# BOTTOM_BRD_v_1_0_3b.net
KiCad netlist of a schematic drawn in EAGLE
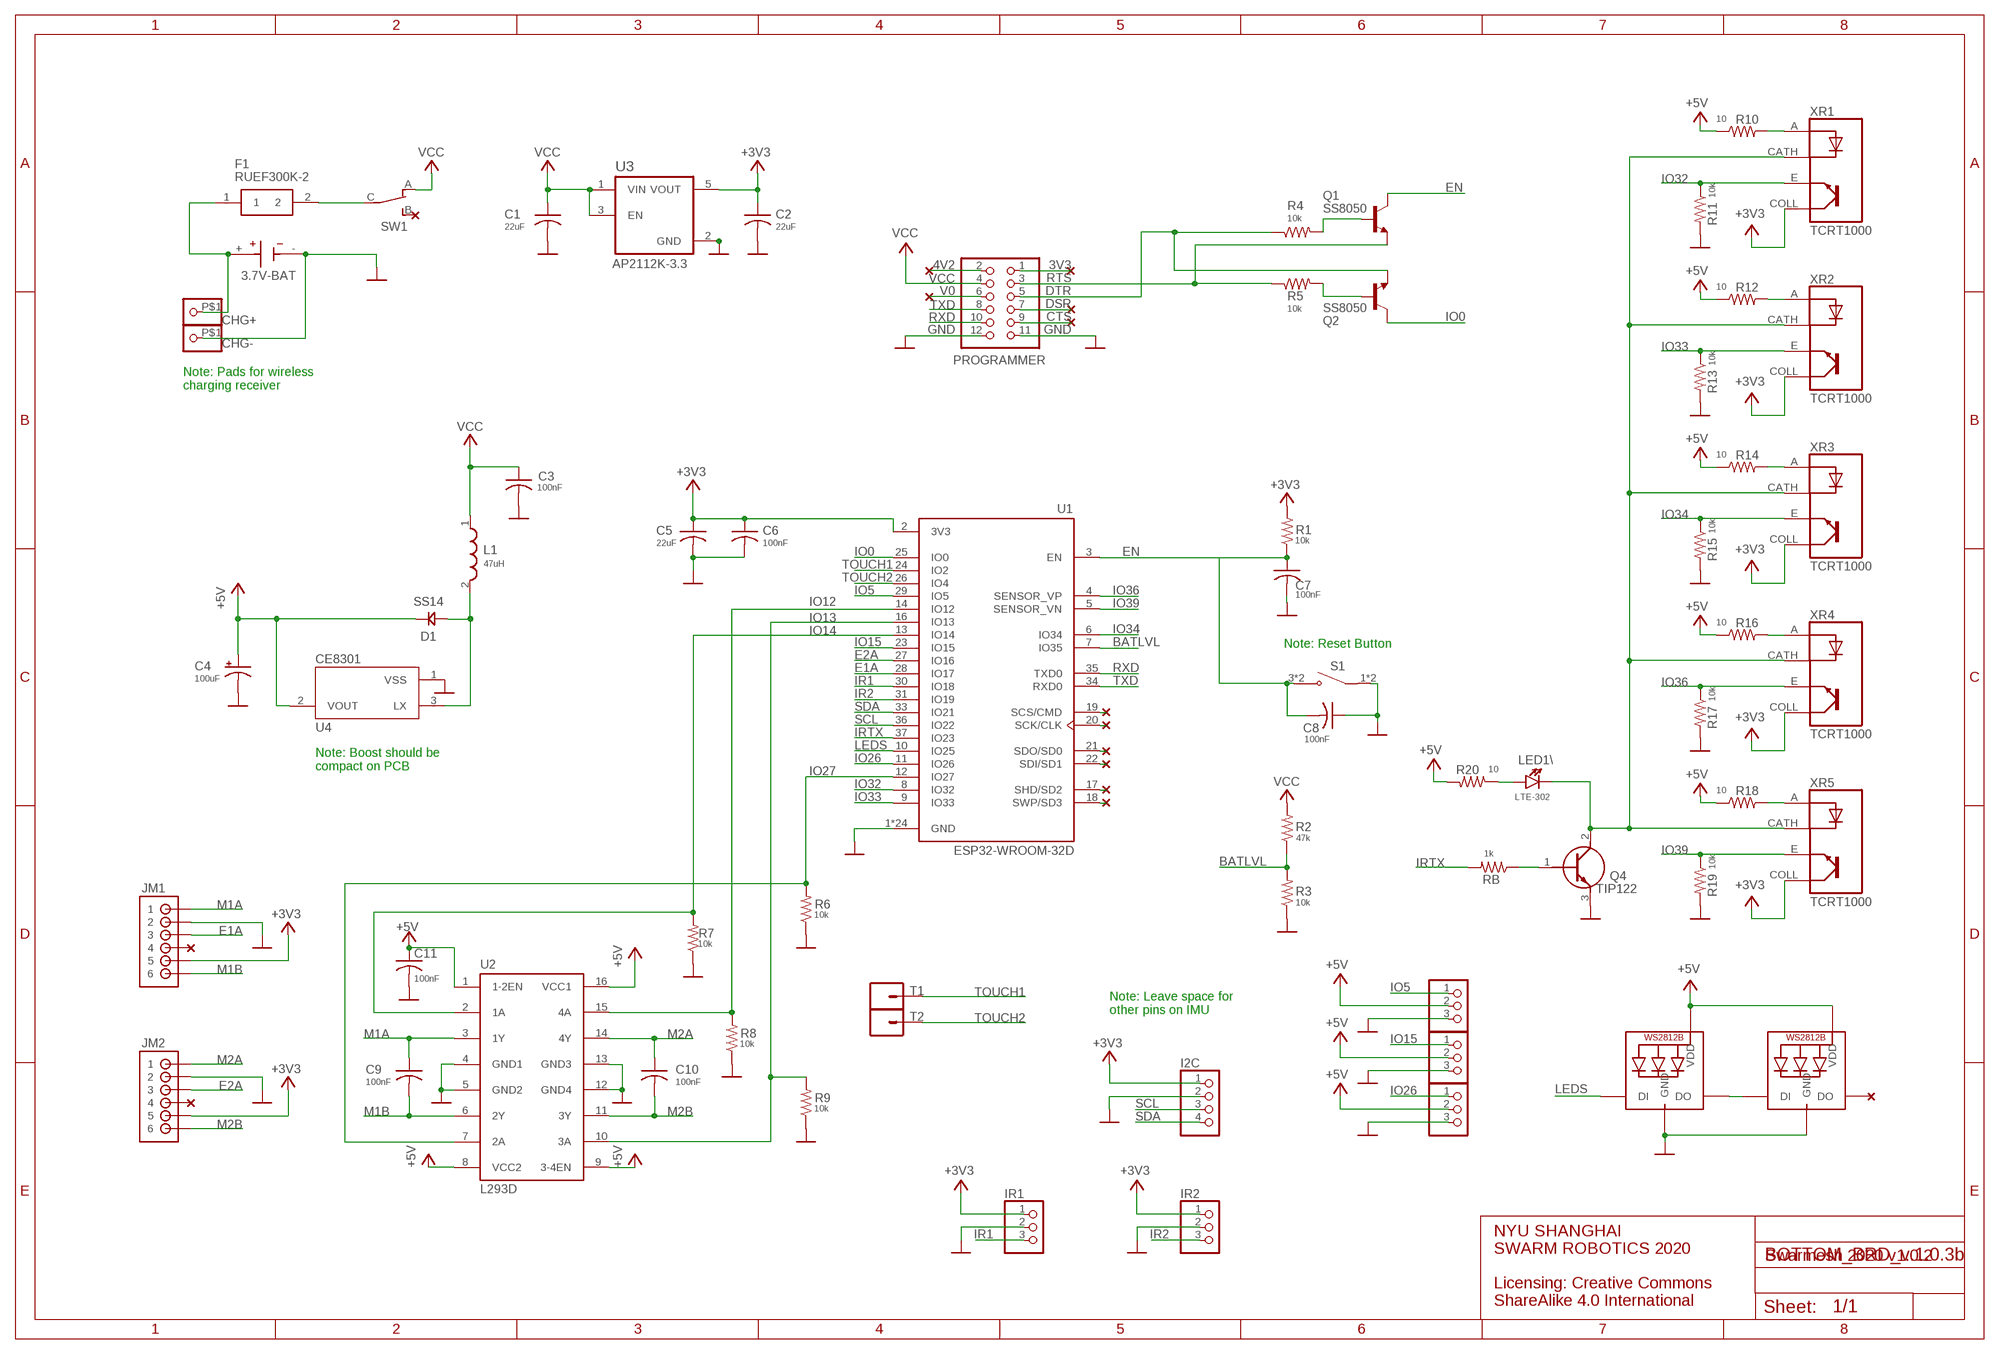
[diagram p0: schematic, sheet 1]

(export (version "E")
  (design (tool "Eeschema 10.0.6"))
  (components
    (comp (ref "BT")
      (value "3.7V-BAT")
      (footprint "eagle-import:BAT_6S-AA")
      (fields (field (name "MF") "MPD") (field (name "MP") "6S-AA"))
      (libsource (lib "eagle-import") (part "6S-AA"))
    )
    (comp (ref "C1")
      (value "22uF")
      (footprint "eagle-import:C0805")
      (libsource (lib "eagle-import") (part "C-USC0805"))
    )
    (comp (ref "C2")
      (value "22uF")
      (footprint "eagle-import:C0805")
      (libsource (lib "eagle-import") (part "C-USC0805"))
    )
    (comp (ref "C3")
      (value "100nF")
      (footprint "eagle-import:C0805")
      (libsource (lib "eagle-import") (part "C-USC0805"))
    )
    (comp (ref "C4")
      (value "100uF")
      (footprint "eagle-import:153CLV-0605")
      (libsource (lib "eagle-import") (part "CPOL-US153CLV-0605"))
    )
    (comp (ref "C5")
      (value "22uF")
      (footprint "eagle-import:C0805")
      (libsource (lib "eagle-import") (part "C-USC0805"))
    )
    (comp (ref "C6")
      (value "100nF")
      (footprint "eagle-import:C0805")
      (libsource (lib "eagle-import") (part "C-USC0805"))
    )
    (comp (ref "C7")
      (value "100nF")
      (footprint "eagle-import:C0805")
      (libsource (lib "eagle-import") (part "C-USC0805"))
    )
    (comp (ref "C8")
      (value "100nF")
      (footprint "eagle-import:C0805")
      (libsource (lib "eagle-import") (part "C-USC0805"))
    )
    (comp (ref "C9")
      (value "100nF")
      (footprint "eagle-import:C0805")
      (libsource (lib "eagle-import") (part "C-USC0805"))
    )
    (comp (ref "C10")
      (value "100nF")
      (footprint "eagle-import:C0805")
      (libsource (lib "eagle-import") (part "C-USC0805"))
    )
    (comp (ref "C11")
      (value "100nF")
      (footprint "eagle-import:C0805")
      (libsource (lib "eagle-import") (part "C-USC0805"))
    )
    (comp (ref "CHARGING")
      (value "WS2812B5050")
      (footprint "eagle-import:WS2812B")
      (libsource (lib "eagle-import") (part "WS2812B5050"))
    )
    (comp (ref "CHG+")
      (value "PINHD-1X1-BIGPOGO")
      (footprint "eagle-import:1X1-BIGPOGO")
      (libsource (lib "eagle-import") (part "PINHD-1X1-BIGPOGO"))
    )
    (comp (ref "CHG-")
      (value "PINHD-1X1-BIGPOGO")
      (footprint "eagle-import:1X1-BIGPOGO")
      (libsource (lib "eagle-import") (part "PINHD-1X1-BIGPOGO"))
    )
    (comp (ref "D1")
      (value "SS14")
      (footprint "eagle-import:DO214")
      (fields (field (name "MF") "ON Semiconductor"))
      (libsource (lib "eagle-import") (part "SS14"))
    )
    (comp (ref "F1")
      (value "RUEF300K-2")
      (footprint "eagle-import:RUEF300K2")
      (libsource (lib "eagle-import") (part "RUEF300K-2"))
    )
    (comp (ref "GPIO5")
      (value "PINHD-1X3")
      (footprint "eagle-import:1X03")
      (libsource (lib "eagle-import") (part "PINHD-1X3"))
    )
    (comp (ref "GPIO15")
      (value "PINHD-1X3")
      (footprint "eagle-import:1X03")
      (libsource (lib "eagle-import") (part "PINHD-1X3"))
    )
    (comp (ref "GPIO26")
      (value "PINHD-1X3")
      (footprint "eagle-import:1X03")
      (libsource (lib "eagle-import") (part "PINHD-1X3"))
    )
    (comp (ref "I2C")
      (value "PINHD-1X4")
      (footprint "eagle-import:1X04")
      (libsource (lib "eagle-import") (part "PINHD-1X4"))
    )
    (comp (ref "IR1")
      (value "PINHD-1X3")
      (footprint "eagle-import:1X03")
      (libsource (lib "eagle-import") (part "PINHD-1X3"))
    )
    (comp (ref "IR2")
      (value "PINHD-1X3")
      (footprint "eagle-import:1X03")
      (libsource (lib "eagle-import") (part "PINHD-1X3"))
    )
    (comp (ref "JM1")
      (value "B6B-ZR")
      (footprint "eagle-import:B6B-ZR")
      (fields (field (name "MF") "JST"))
      (libsource (lib "eagle-import") (part "B6B-ZR"))
    )
    (comp (ref "JM2")
      (value "B6B-ZR")
      (footprint "eagle-import:B6B-ZR")
      (fields (field (name "MF") "JST"))
      (libsource (lib "eagle-import") (part "B6B-ZR"))
    )
    (comp (ref "L1")
      (value "47uH")
      (footprint "eagle-import:INDP5858X480N")
      (fields (field (name "MF") "Bourns") (field (name "MP") "SDR0604-100KL"))
      (libsource (lib "eagle-import") (part "SDR0604-100KL"))
    )
    (comp (ref "LED1\\")
      (value "LTE-302")
      (footprint "eagle-import:LTE-302")
      (fields (field (name "DIGI-KEY_PART_NUMBER") "160-1930-ND") (field (name "MF") "Lite-On Inc."))
      (libsource (lib "eagle-import") (part "LTE-302"))
    )
    (comp (ref "PROGRAMMER")
      (value "PINHD-2X6")
      (footprint "eagle-import:2X06")
      (libsource (lib "eagle-import") (part "PINHD-2X6"))
    )
    (comp (ref "Q1")
      (value "SS8050")
      (footprint "eagle-import:SOT23")
      (libsource (lib "eagle-import") (part "BC850"))
    )
    (comp (ref "Q2")
      (value "SS8050")
      (footprint "eagle-import:SOT23")
      (libsource (lib "eagle-import") (part "BC850"))
    )
    (comp (ref "Q4")
      (value "TIP122")
      (footprint "eagle-import:TO270P460X1020X2008-3P")
      (fields (field (name "MOUSER_PART_NUMBER") "511-TIP122"))
      (libsource (lib "eagle-import") (part "TIP122"))
    )
    (comp (ref "R1")
      (value "10k")
      (footprint "eagle-import:M0805")
      (libsource (lib "eagle-import") (part "R-US_M0805"))
    )
    (comp (ref "R2")
      (value "47k")
      (footprint "eagle-import:M0805")
      (libsource (lib "eagle-import") (part "R-US_M0805"))
    )
    (comp (ref "R3")
      (value "10k")
      (footprint "eagle-import:M0805")
      (libsource (lib "eagle-import") (part "R-US_M0805"))
    )
    (comp (ref "R4")
      (value "10k")
      (footprint "eagle-import:M0805")
      (libsource (lib "eagle-import") (part "R-US_M0805"))
    )
    (comp (ref "R5")
      (value "10k")
      (footprint "eagle-import:M0805")
      (libsource (lib "eagle-import") (part "R-US_M0805"))
    )
    (comp (ref "R6")
      (value "10k")
      (footprint "eagle-import:M0805")
      (libsource (lib "eagle-import") (part "R-US_M0805"))
    )
    (comp (ref "R7")
      (value "10k")
      (footprint "eagle-import:M0805")
      (libsource (lib "eagle-import") (part "R-US_M0805"))
    )
    (comp (ref "R8")
      (value "10k")
      (footprint "eagle-import:M0805")
      (libsource (lib "eagle-import") (part "R-US_M0805"))
    )
    (comp (ref "R9")
      (value "10k")
      (footprint "eagle-import:M0805")
      (libsource (lib "eagle-import") (part "R-US_M0805"))
    )
    (comp (ref "R10")
      (value "10")
      (footprint "eagle-import:M0805")
      (libsource (lib "eagle-import") (part "R-US_M0805"))
    )
    (comp (ref "R11")
      (value "10k")
      (footprint "eagle-import:M0805")
      (libsource (lib "eagle-import") (part "R-US_M0805"))
    )
    (comp (ref "R12")
      (value "10")
      (footprint "eagle-import:M0805")
      (libsource (lib "eagle-import") (part "R-US_M0805"))
    )
    (comp (ref "R13")
      (value "10k")
      (footprint "eagle-import:M0805")
      (libsource (lib "eagle-import") (part "R-US_M0805"))
    )
    (comp (ref "R14")
      (value "10")
      (footprint "eagle-import:M0805")
      (libsource (lib "eagle-import") (part "R-US_M0805"))
    )
    (comp (ref "R15")
      (value "10k")
      (footprint "eagle-import:M0805")
      (libsource (lib "eagle-import") (part "R-US_M0805"))
    )
    (comp (ref "R16")
      (value "10")
      (footprint "eagle-import:M0805")
      (libsource (lib "eagle-import") (part "R-US_M0805"))
    )
    (comp (ref "R17")
      (value "10k")
      (footprint "eagle-import:M0805")
      (libsource (lib "eagle-import") (part "R-US_M0805"))
    )
    (comp (ref "R18")
      (value "10")
      (footprint "eagle-import:M0805")
      (libsource (lib "eagle-import") (part "R-US_M0805"))
    )
    (comp (ref "R19")
      (value "10k")
      (footprint "eagle-import:M0805")
      (libsource (lib "eagle-import") (part "R-US_M0805"))
    )
    (comp (ref "R20")
      (value "10")
      (footprint "eagle-import:M0805")
      (libsource (lib "eagle-import") (part "R-US_M0805"))
    )
    (comp (ref "RB")
      (value "1k")
      (footprint "eagle-import:M0805")
      (libsource (lib "eagle-import") (part "R-US_M0805"))
    )
    (comp (ref "S1")
      (value "2-1437565-9")
      (footprint "eagle-import:SW_2-1437565-9")
      (fields (field (name "MF") "TE Connectivity"))
      (libsource (lib "eagle-import") (part "2-1437565-9"))
    )
    (comp (ref "STATE")
      (value "WS2812B5050")
      (footprint "eagle-import:WS2812B")
      (libsource (lib "eagle-import") (part "WS2812B5050"))
    )
    (comp (ref "SW1")
      (value "CS12ANW03")
      (footprint "eagle-import:CS12ANW03")
      (fields (field (name "MF") "NKK Switches"))
      (libsource (lib "eagle-import") (part "CS12ANW03"))
    )
    (comp (ref "T1")
      (value "CONN_01SPRING-CONN")
      (footprint "eagle-import:SPRING-CONNECTOR")
      (libsource (lib "eagle-import") (part "CONN_01SPRING-CONN"))
    )
    (comp (ref "T2")
      (value "CONN_01SPRING-CONN")
      (footprint "eagle-import:SPRING-CONNECTOR")
      (libsource (lib "eagle-import") (part "CONN_01SPRING-CONN"))
    )
    (comp (ref "U1")
      (value "ESP32-WROOM-32D")
      (footprint "eagle-import:MODULE_ESP32-WROOM-32D")
      (fields (field (name "MF") "Espressif Systems"))
      (libsource (lib "eagle-import") (part "ESP32-WROOM-32D"))
    )
    (comp (ref "U2")
      (value "L293D")
      (footprint "eagle-import:DIL16")
      (libsource (lib "eagle-import") (part "L293D"))
    )
    (comp (ref "U3")
      (value "AP2112K-3.3")
      (footprint "eagle-import:SOT95P285X140-5N")
      (fields (field (name "MF") "Diodes Inc.") (field (name "MP") "AP2112K-3.3TRG1"))
      (libsource (lib "eagle-import") (part "AP2112K-3.3TRG1"))
    )
    (comp (ref "U4")
      (value "CE8301")
      (footprint "eagle-import:REG_MCP1702T-3302E_MB")
      (fields (field (name "MF") "Microchip") (field (name "MP") "MCP1702T-3302E/MB"))
      (libsource (lib "eagle-import") (part "MCP1702T-3302E/MB"))
    )
    (comp (ref "XR1")
      (value "TCRT1000")
      (footprint "eagle-import:XDCR_TCRT1000")
      (fields (field (name "MF") "Vishay"))
      (libsource (lib "eagle-import") (part "TCRT1000"))
    )
    (comp (ref "XR2")
      (value "TCRT1000")
      (footprint "eagle-import:XDCR_TCRT1000")
      (fields (field (name "MF") "Vishay"))
      (libsource (lib "eagle-import") (part "TCRT1000"))
    )
    (comp (ref "XR3")
      (value "TCRT1000")
      (footprint "eagle-import:XDCR_TCRT1000")
      (fields (field (name "MF") "Vishay"))
      (libsource (lib "eagle-import") (part "TCRT1000"))
    )
    (comp (ref "XR4")
      (value "TCRT1000")
      (footprint "eagle-import:XDCR_TCRT1000")
      (fields (field (name "MF") "Vishay"))
      (libsource (lib "eagle-import") (part "TCRT1000"))
    )
    (comp (ref "XR5")
      (value "TCRT1000")
      (footprint "eagle-import:XDCR_TCRT1000")
      (fields (field (name "MF") "Vishay"))
      (libsource (lib "eagle-import") (part "TCRT1000"))
    )
  )
  (nets
    (net (code "1") (name "+3V3") (class "Default")
      (node (ref "C2") (pin "1") (pinfunction "1_1") (pintype "passive"))
      (node (ref "C5") (pin "1") (pinfunction "1_1") (pintype "passive"))
      (node (ref "C6") (pin "1") (pinfunction "1_1") (pintype "passive"))
      (node (ref "I2C") (pin "1") (pinfunction "1_1") (pintype "passive"))
      (node (ref "IR1") (pin "1") (pinfunction "1_1") (pintype "passive"))
      (node (ref "IR2") (pin "1") (pinfunction "1_1") (pintype "passive"))
      (node (ref "JM1") (pin "5") (pinfunction "5_5") (pintype "bidirectional"))
      (node (ref "JM2") (pin "5") (pinfunction "5_5") (pintype "bidirectional"))
      (node (ref "R1") (pin "2") (pinfunction "2_2") (pintype "passive"))
      (node (ref "U1") (pin "2") (pinfunction "3V3_2") (pintype "power_in"))
      (node (ref "U3") (pin "5") (pinfunction "VOUT_5") (pintype "power_in"))
      (node (ref "XR1") (pin "COLL") (pinfunction "CO_COLL") (pintype "passive"))
      (node (ref "XR2") (pin "COLL") (pinfunction "CO_COLL") (pintype "passive"))
      (node (ref "XR3") (pin "COLL") (pinfunction "CO_COLL") (pintype "passive"))
      (node (ref "XR4") (pin "COLL") (pinfunction "CO_COLL") (pintype "passive"))
      (node (ref "XR5") (pin "COLL") (pinfunction "CO_COLL") (pintype "passive"))
    )
    (net (code "2") (name "+5V") (class "Default")
      (node (ref "C11") (pin "1") (pinfunction "1_1") (pintype "passive"))
      (node (ref "C4") (pin "+") (pinfunction "+_+") (pintype "passive"))
      (node (ref "CHARGING") (pin "1-VDD") (pinfunction "VDD_1-VDD") (pintype "power_in"))
      (node (ref "D1") (pin "CATHODE") (pinfunction "KATHODE_CATHODE") (pintype "bidirectional"))
      (node (ref "GPIO15") (pin "2") (pinfunction "2_2") (pintype "passive"))
      (node (ref "GPIO26") (pin "2") (pinfunction "2_2") (pintype "passive"))
      (node (ref "GPIO5") (pin "2") (pinfunction "2_2") (pintype "passive"))
      (node (ref "R10") (pin "1") (pinfunction "1_1") (pintype "passive"))
      (node (ref "R12") (pin "1") (pinfunction "1_1") (pintype "passive"))
      (node (ref "R14") (pin "1") (pinfunction "1_1") (pintype "passive"))
      (node (ref "R16") (pin "1") (pinfunction "1_1") (pintype "passive"))
      (node (ref "R18") (pin "1") (pinfunction "1_1") (pintype "passive"))
      (node (ref "R20") (pin "2") (pinfunction "2_2") (pintype "passive"))
      (node (ref "STATE") (pin "1-VDD") (pinfunction "VDD_1-VDD") (pintype "power_in"))
      (node (ref "U2") (pin "1") (pinfunction "1-2EN_1") (pintype "input"))
      (node (ref "U2") (pin "16") (pinfunction "VCC1_16") (pintype "power_in"))
      (node (ref "U2") (pin "8") (pinfunction "VCC2_8") (pintype "power_in"))
      (node (ref "U2") (pin "9") (pinfunction "3-4EN_9") (pintype "input"))
      (node (ref "U4") (pin "2") (pinfunction "VOUT_2") (pintype "input"))
    )
    (net (code "3") (name "/3V3") (class "Default")
      (node (ref "PROGRAMMER") (pin "1") (pinfunction "1_1") (pintype "passive"))
    )
    (net (code "4") (name "/4V2") (class "Default")
      (node (ref "PROGRAMMER") (pin "2") (pinfunction "2_2") (pintype "passive"))
    )
    (net (code "5") (name "/BATLVL") (class "Default")
      (node (ref "R2") (pin "1") (pinfunction "1_1") (pintype "passive"))
      (node (ref "R3") (pin "2") (pinfunction "2_2") (pintype "passive"))
      (node (ref "U1") (pin "7") (pinfunction "IO35_7") (pintype "input"))
    )
    (net (code "6") (name "/CTS") (class "Default")
      (node (ref "PROGRAMMER") (pin "9") (pinfunction "9_9") (pintype "passive"))
    )
    (net (code "7") (name "/DSR") (class "Default")
      (node (ref "PROGRAMMER") (pin "7") (pinfunction "7_7") (pintype "passive"))
    )
    (net (code "8") (name "/DTR") (class "Default")
      (node (ref "PROGRAMMER") (pin "5") (pinfunction "5_5") (pintype "passive"))
      (node (ref "Q2") (pin "2") (pinfunction "E_2") (pintype "passive"))
      (node (ref "R4") (pin "1") (pinfunction "1_1") (pintype "passive"))
    )
    (net (code "9") (name "/E1A") (class "Default")
      (node (ref "JM1") (pin "3") (pinfunction "3_3") (pintype "bidirectional"))
      (node (ref "U1") (pin "28") (pinfunction "IO17_28") (pintype "bidirectional"))
    )
    (net (code "10") (name "/E2A") (class "Default")
      (node (ref "JM2") (pin "3") (pinfunction "3_3") (pintype "bidirectional"))
      (node (ref "U1") (pin "27") (pinfunction "IO16_27") (pintype "bidirectional"))
    )
    (net (code "11") (name "/EN") (class "Default")
      (node (ref "C7") (pin "1") (pinfunction "1_1") (pintype "passive"))
      (node (ref "C8") (pin "2") (pinfunction "2_2") (pintype "passive"))
      (node (ref "Q1") (pin "3") (pinfunction "C_3") (pintype "passive"))
      (node (ref "R1") (pin "1") (pinfunction "1_1") (pintype "passive"))
      (node (ref "S1") (pin "3") (pinfunction "NO_3") (pintype "passive"))
      (node (ref "S1") (pin "4") (pinfunction "NO_4") (pintype "passive"))
      (node (ref "U1") (pin "3") (pinfunction "EN_3") (pintype "input"))
    )
    (net (code "12") (name "/IO0") (class "Default")
      (node (ref "Q2") (pin "3") (pinfunction "C_3") (pintype "passive"))
      (node (ref "U1") (pin "25") (pinfunction "IO0_25") (pintype "bidirectional"))
    )
    (net (code "13") (name "/IO5") (class "Default")
      (node (ref "GPIO5") (pin "1") (pinfunction "1_1") (pintype "passive"))
      (node (ref "U1") (pin "29") (pinfunction "IO5_29") (pintype "bidirectional"))
    )
    (net (code "14") (name "/IO12") (class "Default")
      (node (ref "R8") (pin "2") (pinfunction "2_2") (pintype "passive"))
      (node (ref "U1") (pin "14") (pinfunction "IO12_14") (pintype "bidirectional"))
      (node (ref "U2") (pin "15") (pinfunction "4A_15") (pintype "input"))
    )
    (net (code "15") (name "/IO13") (class "Default")
      (node (ref "R9") (pin "2") (pinfunction "2_2") (pintype "passive"))
      (node (ref "U1") (pin "16") (pinfunction "IO13_16") (pintype "bidirectional"))
      (node (ref "U2") (pin "10") (pinfunction "3A_10") (pintype "input"))
    )
    (net (code "16") (name "/IO14") (class "Default")
      (node (ref "R7") (pin "2") (pinfunction "2_2") (pintype "passive"))
      (node (ref "U1") (pin "13") (pinfunction "IO14_13") (pintype "bidirectional"))
      (node (ref "U2") (pin "2") (pinfunction "1A_2") (pintype "input"))
    )
    (net (code "17") (name "/IO15") (class "Default")
      (node (ref "GPIO15") (pin "1") (pinfunction "1_1") (pintype "passive"))
      (node (ref "U1") (pin "23") (pinfunction "IO15_23") (pintype "bidirectional"))
    )
    (net (code "18") (name "/IO26") (class "Default")
      (node (ref "GPIO26") (pin "1") (pinfunction "1_1") (pintype "passive"))
      (node (ref "U1") (pin "11") (pinfunction "IO26_11") (pintype "bidirectional"))
    )
    (net (code "19") (name "/IO27") (class "Default")
      (node (ref "R6") (pin "2") (pinfunction "2_2") (pintype "passive"))
      (node (ref "U1") (pin "12") (pinfunction "IO27_12") (pintype "bidirectional"))
      (node (ref "U2") (pin "7") (pinfunction "2A_7") (pintype "input"))
    )
    (net (code "20") (name "/IO32") (class "Default")
      (node (ref "R11") (pin "1") (pinfunction "1_1") (pintype "passive"))
      (node (ref "U1") (pin "8") (pinfunction "IO32_8") (pintype "bidirectional"))
      (node (ref "XR1") (pin "E") (pinfunction "E_E") (pintype "passive"))
    )
    (net (code "21") (name "/IO33") (class "Default")
      (node (ref "R13") (pin "1") (pinfunction "1_1") (pintype "passive"))
      (node (ref "U1") (pin "9") (pinfunction "IO33_9") (pintype "bidirectional"))
      (node (ref "XR2") (pin "E") (pinfunction "E_E") (pintype "passive"))
    )
    (net (code "22") (name "/IO34") (class "Default")
      (node (ref "R15") (pin "1") (pinfunction "1_1") (pintype "passive"))
      (node (ref "U1") (pin "6") (pinfunction "IO34_6") (pintype "input"))
      (node (ref "XR3") (pin "E") (pinfunction "E_E") (pintype "passive"))
    )
    (net (code "23") (name "/IO36") (class "Default")
      (node (ref "R17") (pin "1") (pinfunction "1_1") (pintype "passive"))
      (node (ref "U1") (pin "4") (pinfunction "SENSOR_VP_4") (pintype "input"))
      (node (ref "XR4") (pin "E") (pinfunction "E_E") (pintype "passive"))
    )
    (net (code "24") (name "/IO39") (class "Default")
      (node (ref "R19") (pin "1") (pinfunction "1_1") (pintype "passive"))
      (node (ref "U1") (pin "5") (pinfunction "SENSOR_VN_5") (pintype "input"))
      (node (ref "XR5") (pin "E") (pinfunction "E_E") (pintype "passive"))
    )
    (net (code "25") (name "/IR1") (class "Default")
      (node (ref "IR1") (pin "3") (pinfunction "3_3") (pintype "passive"))
      (node (ref "U1") (pin "30") (pinfunction "IO18_30") (pintype "bidirectional"))
    )
    (net (code "26") (name "/IR2") (class "Default")
      (node (ref "IR2") (pin "3") (pinfunction "3_3") (pintype "passive"))
      (node (ref "U1") (pin "31") (pinfunction "IO19_31") (pintype "bidirectional"))
    )
    (net (code "27") (name "/IRTX") (class "Default")
      (node (ref "RB") (pin "2") (pinfunction "2_2") (pintype "passive"))
      (node (ref "U1") (pin "37") (pinfunction "IO23_37") (pintype "bidirectional"))
    )
    (net (code "28") (name "/LEDS") (class "Default")
      (node (ref "CHARGING") (pin "4-DIN") (pinfunction "DI_4-DIN") (pintype "input"))
      (node (ref "U1") (pin "10") (pinfunction "IO25_10") (pintype "bidirectional"))
    )
    (net (code "29") (name "/M1A") (class "Default")
      (node (ref "C9") (pin "1") (pinfunction "1_1") (pintype "passive"))
      (node (ref "JM1") (pin "1") (pinfunction "1_1") (pintype "bidirectional"))
      (node (ref "U2") (pin "3") (pinfunction "1Y_3") (pintype "output"))
    )
    (net (code "30") (name "/M1B") (class "Default")
      (node (ref "C9") (pin "2") (pinfunction "2_2") (pintype "passive"))
      (node (ref "JM1") (pin "6") (pinfunction "6_6") (pintype "bidirectional"))
      (node (ref "U2") (pin "6") (pinfunction "2Y_6") (pintype "output"))
    )
    (net (code "31") (name "/M2A") (class "Default")
      (node (ref "C10") (pin "1") (pinfunction "1_1") (pintype "passive"))
      (node (ref "JM2") (pin "1") (pinfunction "1_1") (pintype "bidirectional"))
      (node (ref "U2") (pin "14") (pinfunction "4Y_14") (pintype "output"))
    )
    (net (code "32") (name "/M2B") (class "Default")
      (node (ref "C10") (pin "2") (pinfunction "2_2") (pintype "passive"))
      (node (ref "JM2") (pin "6") (pinfunction "6_6") (pintype "bidirectional"))
      (node (ref "U2") (pin "11") (pinfunction "3Y_11") (pintype "output"))
    )
    (net (code "33") (name "/RTS") (class "Default")
      (node (ref "PROGRAMMER") (pin "3") (pinfunction "3_3") (pintype "passive"))
      (node (ref "Q1") (pin "2") (pinfunction "E_2") (pintype "passive"))
      (node (ref "R5") (pin "1") (pinfunction "1_1") (pintype "passive"))
    )
    (net (code "34") (name "/RXD") (class "Default")
      (node (ref "PROGRAMMER") (pin "10") (pinfunction "10_10") (pintype "passive"))
      (node (ref "U1") (pin "35") (pinfunction "TXD0_35") (pintype "bidirectional"))
    )
    (net (code "35") (name "/SCL") (class "Default")
      (node (ref "I2C") (pin "3") (pinfunction "3_3") (pintype "passive"))
      (node (ref "U1") (pin "36") (pinfunction "IO22_36") (pintype "bidirectional"))
    )
    (net (code "36") (name "/SDA") (class "Default")
      (node (ref "I2C") (pin "4") (pinfunction "4_4") (pintype "passive"))
      (node (ref "U1") (pin "33") (pinfunction "IO21_33") (pintype "bidirectional"))
    )
    (net (code "37") (name "/TOUCH1") (class "Default")
      (node (ref "T1") (pin "P$2") (pinfunction "1_P$2") (pintype "passive"))
      (node (ref "U1") (pin "24") (pinfunction "IO2_24") (pintype "bidirectional"))
    )
    (net (code "38") (name "/TOUCH2") (class "Default")
      (node (ref "T2") (pin "P$2") (pinfunction "1_P$2") (pintype "passive"))
      (node (ref "U1") (pin "26") (pinfunction "IO4_26") (pintype "bidirectional"))
    )
    (net (code "39") (name "/TXD") (class "Default")
      (node (ref "PROGRAMMER") (pin "8") (pinfunction "8_8") (pintype "passive"))
      (node (ref "U1") (pin "34") (pinfunction "RXD0_34") (pintype "bidirectional"))
    )
    (net (code "40") (name "/V0") (class "Default")
      (node (ref "PROGRAMMER") (pin "6") (pinfunction "6_6") (pintype "passive"))
    )
    (net (code "41") (name "GND") (class "Default")
      (node (ref "BT") (pin "-") (pinfunction "-_-") (pintype "passive"))
      (node (ref "C1") (pin "2") (pinfunction "2_2") (pintype "passive"))
      (node (ref "C11") (pin "2") (pinfunction "2_2") (pintype "passive"))
      (node (ref "C2") (pin "2") (pinfunction "2_2") (pintype "passive"))
      (node (ref "C3") (pin "2") (pinfunction "2_2") (pintype "passive"))
      (node (ref "C4") (pin "-") (pinfunction "-_-") (pintype "passive"))
      (node (ref "C5") (pin "2") (pinfunction "2_2") (pintype "passive"))
      (node (ref "C6") (pin "2") (pinfunction "2_2") (pintype "passive"))
      (node (ref "C7") (pin "2") (pinfunction "2_2") (pintype "passive"))
      (node (ref "C8") (pin "1") (pinfunction "1_1") (pintype "passive"))
      (node (ref "CHARGING") (pin "3-GND") (pinfunction "GND_3-GND") (pintype "power_in"))
      (node (ref "CHG-") (pin "P$1") (pinfunction "1_P$1") (pintype "passive"))
      (node (ref "GPIO15") (pin "3") (pinfunction "3_3") (pintype "passive"))
      (node (ref "GPIO26") (pin "3") (pinfunction "3_3") (pintype "passive"))
      (node (ref "GPIO5") (pin "3") (pinfunction "3_3") (pintype "passive"))
      (node (ref "I2C") (pin "2") (pinfunction "2_2") (pintype "passive"))
      (node (ref "IR1") (pin "2") (pinfunction "2_2") (pintype "passive"))
      (node (ref "IR2") (pin "2") (pinfunction "2_2") (pintype "passive"))
      (node (ref "JM1") (pin "2") (pinfunction "2_2") (pintype "bidirectional"))
      (node (ref "JM2") (pin "2") (pinfunction "2_2") (pintype "bidirectional"))
      (node (ref "PROGRAMMER") (pin "11") (pinfunction "11_11") (pintype "passive"))
      (node (ref "PROGRAMMER") (pin "12") (pinfunction "12_12") (pintype "passive"))
      (node (ref "Q4") (pin "3") (pinfunction "E_3") (pintype "bidirectional"))
      (node (ref "R11") (pin "2") (pinfunction "2_2") (pintype "passive"))
      (node (ref "R13") (pin "2") (pinfunction "2_2") (pintype "passive"))
      (node (ref "R15") (pin "2") (pinfunction "2_2") (pintype "passive"))
      (node (ref "R17") (pin "2") (pinfunction "2_2") (pintype "passive"))
      (node (ref "R19") (pin "2") (pinfunction "2_2") (pintype "passive"))
      (node (ref "R3") (pin "1") (pinfunction "1_1") (pintype "passive"))
      (node (ref "R6") (pin "1") (pinfunction "1_1") (pintype "passive"))
      (node (ref "R7") (pin "1") (pinfunction "1_1") (pintype "passive"))
      (node (ref "R8") (pin "1") (pinfunction "1_1") (pintype "passive"))
      (node (ref "R9") (pin "1") (pinfunction "1_1") (pintype "passive"))
      (node (ref "S1") (pin "1") (pinfunction "COM_1") (pintype "passive"))
      (node (ref "S1") (pin "2") (pinfunction "COM_2") (pintype "passive"))
      (node (ref "STATE") (pin "3-GND") (pinfunction "GND_3-GND") (pintype "power_in"))
      (node (ref "U1") (pin "1") (pinfunction "GND_1") (pintype "power_in"))
      (node (ref "U1") (pin "15") (pinfunction "GND_15") (pintype "power_in"))
      (node (ref "U1") (pin "38") (pinfunction "GND_38") (pintype "power_in"))
      (node (ref "U1") (pin "39_1") (pinfunction "GND_39_1") (pintype "power_in"))
      (node (ref "U1") (pin "39_10") (pinfunction "GND_39_10") (pintype "power_in"))
      (node (ref "U1") (pin "39_11") (pinfunction "GND_39_11") (pintype "power_in"))
      (node (ref "U1") (pin "39_12") (pinfunction "GND_39_12") (pintype "power_in"))
      (node (ref "U1") (pin "39_13") (pinfunction "GND_39_13") (pintype "power_in"))
      (node (ref "U1") (pin "39_14") (pinfunction "GND_39_14") (pintype "power_in"))
      (node (ref "U1") (pin "39_15") (pinfunction "GND_39_15") (pintype "power_in"))
      (node (ref "U1") (pin "39_16") (pinfunction "GND_39_16") (pintype "power_in"))
      (node (ref "U1") (pin "39_17") (pinfunction "GND_39_17") (pintype "power_in"))
      (node (ref "U1") (pin "39_18") (pinfunction "GND_39_18") (pintype "power_in"))
      (node (ref "U1") (pin "39_19") (pinfunction "GND_39_19") (pintype "power_in"))
      (node (ref "U1") (pin "39_2") (pinfunction "GND_39_2") (pintype "power_in"))
      (node (ref "U1") (pin "39_20") (pinfunction "GND_39_20") (pintype "power_in"))
      (node (ref "U1") (pin "39_21") (pinfunction "GND_39_21") (pintype "power_in"))
      (node (ref "U1") (pin "39_3") (pinfunction "GND_39_3") (pintype "power_in"))
      (node (ref "U1") (pin "39_4") (pinfunction "GND_39_4") (pintype "power_in"))
      (node (ref "U1") (pin "39_5") (pinfunction "GND_39_5") (pintype "power_in"))
      (node (ref "U1") (pin "39_6") (pinfunction "GND_39_6") (pintype "power_in"))
      (node (ref "U1") (pin "39_7") (pinfunction "GND_39_7") (pintype "power_in"))
      (node (ref "U1") (pin "39_8") (pinfunction "GND_39_8") (pintype "power_in"))
      (node (ref "U1") (pin "39_9") (pinfunction "GND_39_9") (pintype "power_in"))
      (node (ref "U2") (pin "12") (pinfunction "GND4_12") (pintype "power_in"))
      (node (ref "U2") (pin "13") (pinfunction "GND3_13") (pintype "power_in"))
      (node (ref "U2") (pin "4") (pinfunction "GND1_4") (pintype "power_in"))
      (node (ref "U2") (pin "5") (pinfunction "GND2_5") (pintype "power_in"))
      (node (ref "U3") (pin "2") (pinfunction "GND_2") (pintype "power_in"))
      (node (ref "U4") (pin "1") (pinfunction "VSS_1") (pintype "power_in"))
    )
    (net (code "42") (name "Net-(CHARGING-DO)") (class "Default")
      (node (ref "CHARGING") (pin "2-DOUT") (pinfunction "DO_2-DOUT") (pintype "output"))
      (node (ref "STATE") (pin "4-DIN") (pinfunction "DI_4-DIN") (pintype "input"))
    )
    (net (code "43") (name "Net-(CHG+-1)") (class "Default")
      (node (ref "BT") (pin "+") (pinfunction "+_+") (pintype "passive"))
      (node (ref "CHG+") (pin "P$1") (pinfunction "1_P$1") (pintype "passive"))
      (node (ref "F1") (pin "1") (pinfunction "1_1") (pintype "bidirectional"))
    )
    (net (code "44") (name "Net-(F1-Pad2)") (class "Default")
      (node (ref "F1") (pin "2") (pinfunction "2_2") (pintype "bidirectional"))
      (node (ref "SW1") (pin "C") (pinfunction "C_C") (pintype "passive"))
    )
    (net (code "45") (name "Net-(LED1\\-PadA)") (class "Default")
      (node (ref "LED1\\") (pin "A") (pinfunction "A_A") (pintype "bidirectional"))
      (node (ref "R20") (pin "1") (pinfunction "1_1") (pintype "passive"))
    )
    (net (code "46") (name "Net-(Q1-B)") (class "Default")
      (node (ref "Q1") (pin "1") (pinfunction "B_1") (pintype "passive"))
      (node (ref "R4") (pin "2") (pinfunction "2_2") (pintype "passive"))
    )
    (net (code "47") (name "Net-(Q2-B)") (class "Default")
      (node (ref "Q2") (pin "1") (pinfunction "B_1") (pintype "passive"))
      (node (ref "R5") (pin "2") (pinfunction "2_2") (pintype "passive"))
    )
    (net (code "48") (name "Net-(Q4-B)") (class "Default")
      (node (ref "Q4") (pin "1") (pinfunction "B_1") (pintype "bidirectional"))
      (node (ref "RB") (pin "1") (pinfunction "1_1") (pintype "passive"))
    )
    (net (code "49") (name "Net-(Q4-C)") (class "Default")
      (node (ref "LED1\\") (pin "C") (pinfunction "C_C") (pintype "bidirectional"))
      (node (ref "Q4") (pin "2") (pinfunction "C_2") (pintype "bidirectional"))
      (node (ref "XR1") (pin "CATH") (pinfunction "C_CATH") (pintype "passive"))
      (node (ref "XR2") (pin "CATH") (pinfunction "C_CATH") (pintype "passive"))
      (node (ref "XR3") (pin "CATH") (pinfunction "C_CATH") (pintype "passive"))
      (node (ref "XR4") (pin "CATH") (pinfunction "C_CATH") (pintype "passive"))
      (node (ref "XR5") (pin "CATH") (pinfunction "C_CATH") (pintype "passive"))
    )
    (net (code "50") (name "Net-(R10-Pad2)") (class "Default")
      (node (ref "R10") (pin "2") (pinfunction "2_2") (pintype "passive"))
      (node (ref "XR1") (pin "A") (pinfunction "A_A") (pintype "passive"))
    )
    (net (code "51") (name "Net-(R12-Pad2)") (class "Default")
      (node (ref "R12") (pin "2") (pinfunction "2_2") (pintype "passive"))
      (node (ref "XR2") (pin "A") (pinfunction "A_A") (pintype "passive"))
    )
    (net (code "52") (name "Net-(R14-Pad2)") (class "Default")
      (node (ref "R14") (pin "2") (pinfunction "2_2") (pintype "passive"))
      (node (ref "XR3") (pin "A") (pinfunction "A_A") (pintype "passive"))
    )
    (net (code "53") (name "Net-(R16-Pad2)") (class "Default")
      (node (ref "R16") (pin "2") (pinfunction "2_2") (pintype "passive"))
      (node (ref "XR4") (pin "A") (pinfunction "A_A") (pintype "passive"))
    )
    (net (code "54") (name "Net-(R18-Pad2)") (class "Default")
      (node (ref "R18") (pin "2") (pinfunction "2_2") (pintype "passive"))
      (node (ref "XR5") (pin "A") (pinfunction "A_A") (pintype "passive"))
    )
    (net (code "55") (name "Net-(U4-LX)") (class "Default")
      (node (ref "D1") (pin "ANODE") (pinfunction "ANODE_ANODE") (pintype "bidirectional"))
      (node (ref "L1") (pin "2") (pinfunction "2_2") (pintype "passive"))
      (node (ref "U4") (pin "3") (pinfunction "LX_3") (pintype "output"))
    )
    (net (code "56") (name "VCC") (class "Default")
      (node (ref "C1") (pin "1") (pinfunction "1_1") (pintype "passive"))
      (node (ref "C3") (pin "1") (pinfunction "1_1") (pintype "passive"))
      (node (ref "L1") (pin "1") (pinfunction "1_1") (pintype "passive"))
      (node (ref "PROGRAMMER") (pin "4") (pinfunction "4_4") (pintype "passive"))
      (node (ref "R2") (pin "2") (pinfunction "2_2") (pintype "passive"))
      (node (ref "SW1") (pin "A") (pinfunction "A_A") (pintype "passive"))
      (node (ref "U3") (pin "1") (pinfunction "VIN_1") (pintype "power_in"))
      (node (ref "U3") (pin "3") (pinfunction "EN_3") (pintype "input"))
    )
    (net (code "57") (name "unconnected-(JM1-Pad4)") (class "Default")
      (node (ref "JM1") (pin "4") (pinfunction "4_4") (pintype "bidirectional"))
    )
    (net (code "58") (name "unconnected-(JM2-Pad4)") (class "Default")
      (node (ref "JM2") (pin "4") (pinfunction "4_4") (pintype "bidirectional"))
    )
    (net (code "59") (name "unconnected-(STATE-DO-Pad2-DOUT)") (class "Default")
      (node (ref "STATE") (pin "2-DOUT") (pinfunction "DO_2-DOUT") (pintype "output"))
    )
    (net (code "60") (name "unconnected-(SW1-PadB)") (class "Default")
      (node (ref "SW1") (pin "B") (pinfunction "B_B") (pintype "passive"))
    )
    (net (code "61") (name "unconnected-(U1-SCK{slash}CLK-Pad20)") (class "Default")
      (node (ref "U1") (pin "20") (pinfunction "SCK/CLK_20") (pintype "bidirectional"))
    )
    (net (code "62") (name "unconnected-(U1-SCS{slash}CMD-Pad19)") (class "Default")
      (node (ref "U1") (pin "19") (pinfunction "SCS/CMD_19") (pintype "bidirectional"))
    )
    (net (code "63") (name "unconnected-(U1-SDI{slash}SD1-Pad22)") (class "Default")
      (node (ref "U1") (pin "22") (pinfunction "SDI/SD1_22") (pintype "bidirectional"))
    )
    (net (code "64") (name "unconnected-(U1-SDO{slash}SD0-Pad21)") (class "Default")
      (node (ref "U1") (pin "21") (pinfunction "SDO/SD0_21") (pintype "bidirectional"))
    )
    (net (code "65") (name "unconnected-(U1-SHD{slash}SD2-Pad17)") (class "Default")
      (node (ref "U1") (pin "17") (pinfunction "SHD/SD2_17") (pintype "bidirectional"))
    )
    (net (code "66") (name "unconnected-(U1-SWP{slash}SD3-Pad18)") (class "Default")
      (node (ref "U1") (pin "18") (pinfunction "SWP/SD3_18") (pintype "bidirectional"))
    )
  )
)
